# emmc.net
KiCad netlist of a schematic drawn in Altium Designer
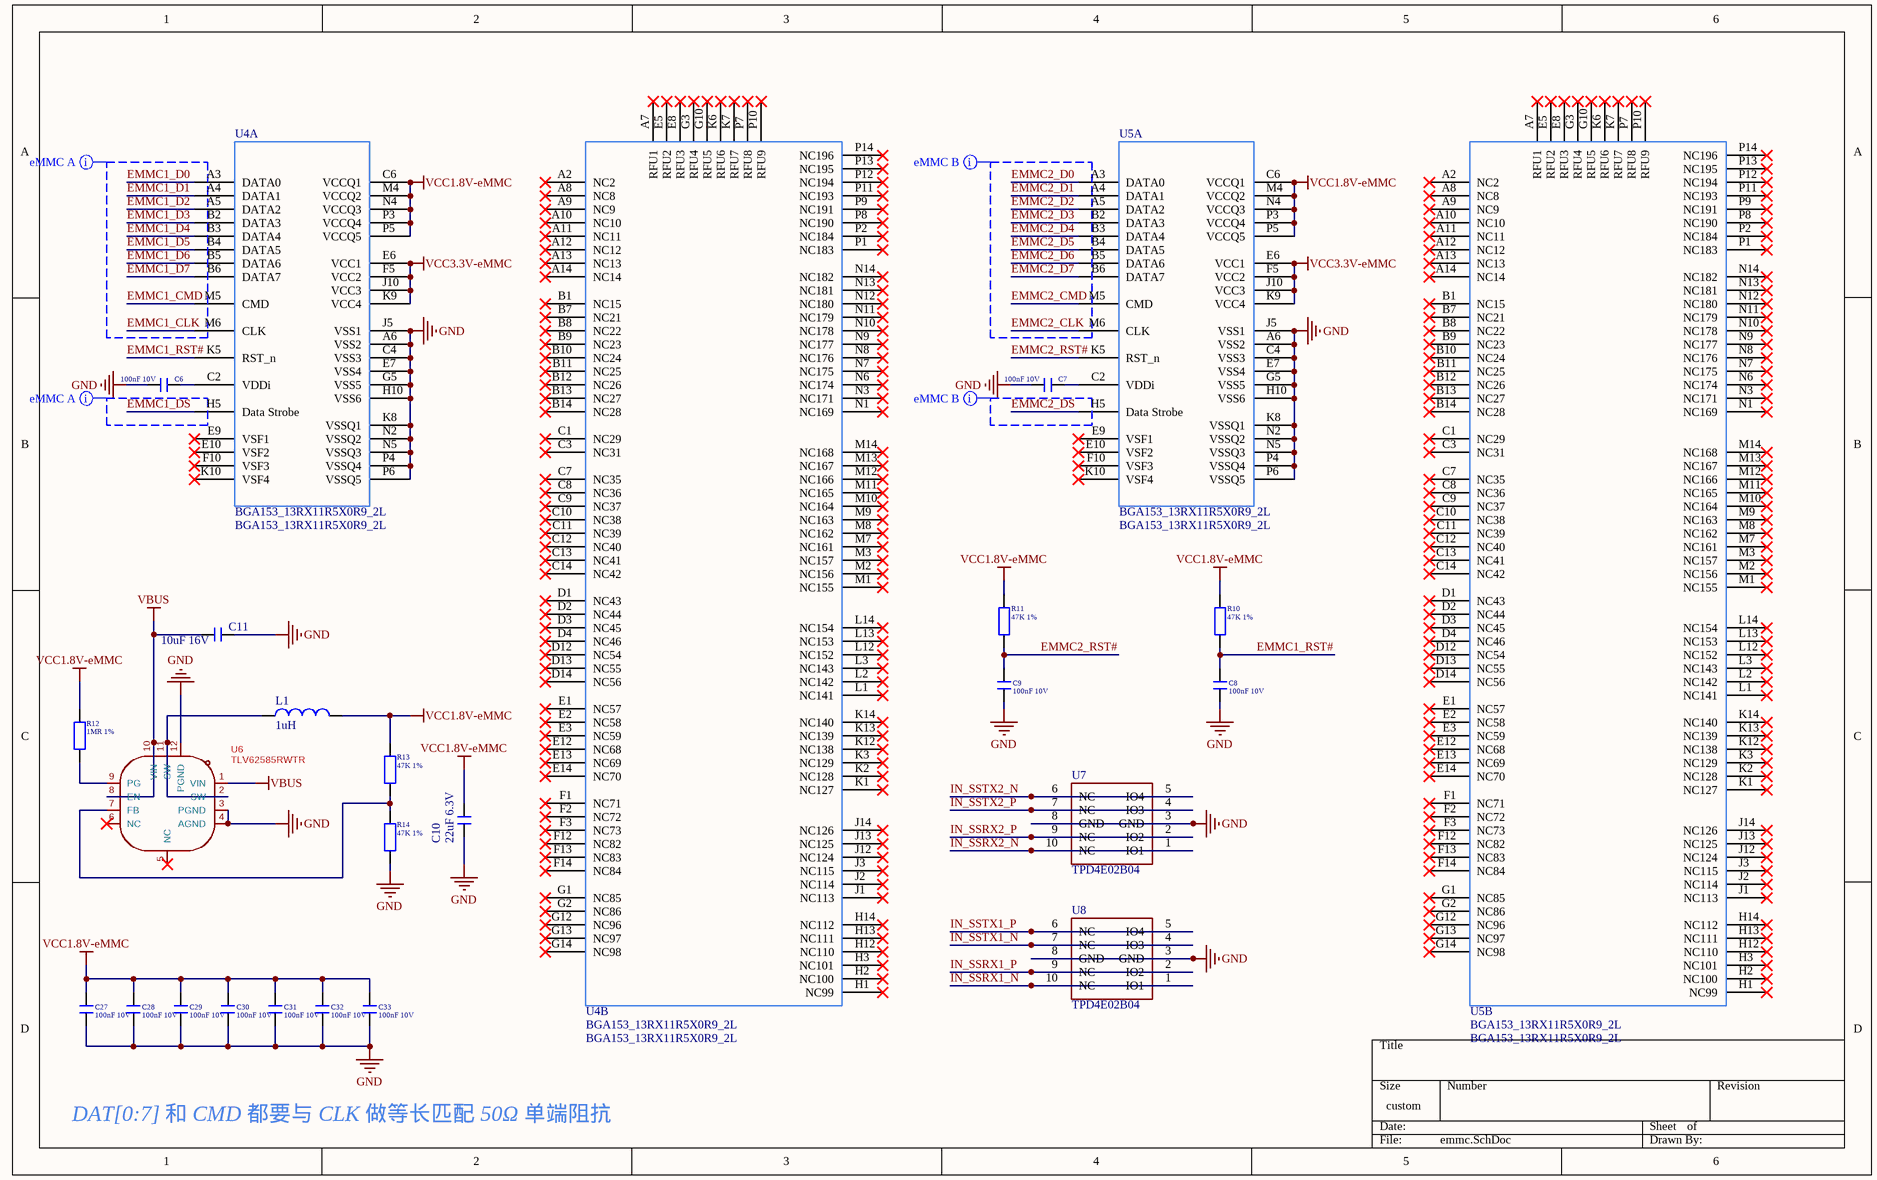
[diagram p0: emmc.SchDoc]

(export (version "E")
  (design (tool "Eeschema 10.0.6"))
  (components
    (comp (ref "C6")
      (value "100nF 10V")
      (footprint "C0402_NS")
      (description "无极性贴片电容")
      (libsource (lib "Capacitor") (part "C"))
    )
    (comp (ref "C7")
      (value "100nF 10V")
      (footprint "C0402_NS")
      (description "无极性贴片电容")
      (libsource (lib "Capacitor") (part "C"))
    )
    (comp (ref "C8")
      (value "100nF 10V")
      (footprint "C0402_NS")
      (description "无极性贴片电容")
      (libsource (lib "Capacitor") (part "C"))
    )
    (comp (ref "C9")
      (value "100nF 10V")
      (footprint "C0402_NS")
      (description "无极性贴片电容")
      (libsource (lib "Capacitor") (part "C"))
    )
    (comp (ref "C10")
      (value "22uF 6.3V")
      (footprint "C0402_NS")
      (description "无极性贴片电容")
      (libsource (lib "Capacitor") (part "C"))
    )
    (comp (ref "C11")
      (value "10uF 16V")
      (footprint "C0402_NS")
      (description "无极性贴片电容")
      (libsource (lib "Capacitor") (part "C"))
    )
    (comp (ref "C27")
      (value "100nF 10V")
      (footprint "C0603_NS")
      (description "无极性贴片电容")
      (libsource (lib "Capacitor") (part "C"))
    )
    (comp (ref "C28")
      (value "100nF 10V")
      (footprint "C0603_NS")
      (description "无极性贴片电容")
      (libsource (lib "Capacitor") (part "C"))
    )
    (comp (ref "C29")
      (value "100nF 10V")
      (footprint "C0603_NS")
      (description "无极性贴片电容")
      (libsource (lib "Capacitor") (part "C"))
    )
    (comp (ref "C30")
      (value "100nF 10V")
      (footprint "C0603_NS")
      (description "无极性贴片电容")
      (libsource (lib "Capacitor") (part "C"))
    )
    (comp (ref "C31")
      (value "100nF 10V")
      (footprint "C0603_NS")
      (description "无极性贴片电容")
      (libsource (lib "Capacitor") (part "C"))
    )
    (comp (ref "C32")
      (value "100nF 10V")
      (footprint "C0603_NS")
      (description "无极性贴片电容")
      (libsource (lib "Capacitor") (part "C"))
    )
    (comp (ref "C33")
      (value "100nF 10V")
      (footprint "C0603_NS")
      (description "无极性贴片电容")
      (libsource (lib "Capacitor") (part "C"))
    )
    (comp (ref "L1")
      (value "1uH")
      (footprint "L 0805_L")
      (description "小功率贴片电感")
      (libsource (lib "Inductor") (part "L"))
    )
    (comp (ref "R10")
      (value "47K 1%")
      (footprint "R0402_NS")
      (description "贴片电阻")
      (libsource (lib "Resistor") (part "R"))
    )
    (comp (ref "R11")
      (value "47K 1%")
      (footprint "R0402_NS")
      (description "贴片电阻")
      (libsource (lib "Resistor") (part "R"))
    )
    (comp (ref "R12")
      (value "1MR 1%")
      (footprint "R0402_NS")
      (description "贴片电阻")
      (libsource (lib "Resistor") (part "R"))
    )
    (comp (ref "R13")
      (value "47K 1%")
      (footprint "R0402_NS")
      (description "贴片电阻")
      (libsource (lib "Resistor") (part "R"))
    )
    (comp (ref "R14")
      (value "47K 1%")
      (footprint "R0402_NS")
      (description "贴片电阻")
      (libsource (lib "Resistor") (part "R"))
    )
    (comp (ref "U4")
      (value "BGA153_13RX11R5X0R9_2L")
      (footprint "FBGA-153_L13.0-W11.5-P0.50_KLMAG1JETD-B041")
      (description "EMMC_B153_2L,更好的满足工艺需求，Fanout方式部分走线跨接再球位上，挖除A1\\C5球位")
      (fields (field (name "PCB FOOTPRINT") "BGA153_13RX11R5X0R9_2L"))
      (libsource (lib "DDR2-DDR3-LPDDR4-RMII PHY") (part "INAND_EMMC_153_2L"))
    )
    (comp (ref "U5")
      (value "BGA153_13RX11R5X0R9_2L")
      (footprint "FBGA-153_L13.0-W11.5-P0.50_KLMAG1JETD-B041")
      (description "EMMC_B153_2L,更好的满足工艺需求，Fanout方式部分走线跨接再球位上，挖除A1\\C5球位")
      (fields (field (name "PCB FOOTPRINT") "BGA153_13RX11R5X0R9_2L"))
      (libsource (lib "DDR2-DDR3-LPDDR4-RMII PHY") (part "INAND_EMMC_153_2L"))
    )
    (comp (ref "U6")
      (value "TLV62585RWTR")
      (footprint "VQFN-HR-12_L2.0-W2.0-P0.50-BL")
      (description "功能类型:降压型;输出类型:可调;工作电压:2.5V~5.5V;输出电压:600mV~5.5V;输出电流:3A;")
      (fields (field (name "MANUFACTURER") "TI(德州仪器)"))
      (libsource (lib "DCDC Convert") (part "TLV62585RWTR"))
    )
    (comp (ref "U7")
      (value "TPD4E02B04")
      (footprint "DIO_TPD4E02B04DQAR")
      (description "ESD")
      (libsource (lib "Diode") (part "TPD4E02B04"))
    )
    (comp (ref "U8")
      (value "TPD4E02B04")
      (footprint "DIO_TPD4E02B04DQAR")
      (description "ESD")
      (libsource (lib "Diode") (part "TPD4E02B04"))
    )
  )
  (nets
    (net (code "1") (name "/EMMC1_CLK") (class "Default")
      (node (ref "U4") (pin "M6") (pinfunction "CLK_M6") (pintype "passive"))
    )
    (net (code "2") (name "/EMMC1_CMD") (class "Default")
      (node (ref "U4") (pin "M5") (pinfunction "CMD_M5") (pintype "passive"))
    )
    (net (code "3") (name "/EMMC1_D0") (class "Default")
      (node (ref "U4") (pin "A3") (pinfunction "DATA0_A3") (pintype "passive"))
    )
    (net (code "4") (name "/EMMC1_D1") (class "Default")
      (node (ref "U4") (pin "A4") (pinfunction "DATA1_A4") (pintype "passive"))
    )
    (net (code "5") (name "/EMMC1_D2") (class "Default")
      (node (ref "U4") (pin "A5") (pinfunction "DATA2_A5") (pintype "passive"))
    )
    (net (code "6") (name "/EMMC1_D3") (class "Default")
      (node (ref "U4") (pin "B2") (pinfunction "DATA3_B2") (pintype "passive"))
    )
    (net (code "7") (name "/EMMC1_D4") (class "Default")
      (node (ref "U4") (pin "B3") (pinfunction "DATA4_B3") (pintype "passive"))
    )
    (net (code "8") (name "/EMMC1_D5") (class "Default")
      (node (ref "U4") (pin "B4") (pinfunction "DATA5_B4") (pintype "passive"))
    )
    (net (code "9") (name "/EMMC1_D6") (class "Default")
      (node (ref "U4") (pin "B5") (pinfunction "DATA6_B5") (pintype "passive"))
    )
    (net (code "10") (name "/EMMC1_D7") (class "Default")
      (node (ref "U4") (pin "B6") (pinfunction "DATA7_B6") (pintype "passive"))
    )
    (net (code "11") (name "/EMMC1_DS") (class "Default")
      (node (ref "U4") (pin "H5") (pinfunction "Data_Strobe_H5") (pintype "passive"))
    )
    (net (code "12") (name "/EMMC1_RST#") (class "Default")
      (node (ref "C8") (pin "1") (pinfunction "1_1") (pintype "passive"))
      (node (ref "R10") (pin "2") (pinfunction "2_2") (pintype "passive"))
      (node (ref "U4") (pin "K5") (pinfunction "RST_n_K5") (pintype "passive"))
    )
    (net (code "13") (name "/EMMC2_CLK") (class "Default")
      (node (ref "U5") (pin "M6") (pinfunction "CLK_M6") (pintype "passive"))
    )
    (net (code "14") (name "/EMMC2_CMD") (class "Default")
      (node (ref "U5") (pin "M5") (pinfunction "CMD_M5") (pintype "passive"))
    )
    (net (code "15") (name "/EMMC2_D0") (class "Default")
      (node (ref "U5") (pin "A3") (pinfunction "DATA0_A3") (pintype "passive"))
    )
    (net (code "16") (name "/EMMC2_D1") (class "Default")
      (node (ref "U5") (pin "A4") (pinfunction "DATA1_A4") (pintype "passive"))
    )
    (net (code "17") (name "/EMMC2_D2") (class "Default")
      (node (ref "U5") (pin "A5") (pinfunction "DATA2_A5") (pintype "passive"))
    )
    (net (code "18") (name "/EMMC2_D3") (class "Default")
      (node (ref "U5") (pin "B2") (pinfunction "DATA3_B2") (pintype "passive"))
    )
    (net (code "19") (name "/EMMC2_D4") (class "Default")
      (node (ref "U5") (pin "B3") (pinfunction "DATA4_B3") (pintype "passive"))
    )
    (net (code "20") (name "/EMMC2_D5") (class "Default")
      (node (ref "U5") (pin "B4") (pinfunction "DATA5_B4") (pintype "passive"))
    )
    (net (code "21") (name "/EMMC2_D6") (class "Default")
      (node (ref "U5") (pin "B5") (pinfunction "DATA6_B5") (pintype "passive"))
    )
    (net (code "22") (name "/EMMC2_D7") (class "Default")
      (node (ref "U5") (pin "B6") (pinfunction "DATA7_B6") (pintype "passive"))
    )
    (net (code "23") (name "/EMMC2_DS") (class "Default")
      (node (ref "U5") (pin "H5") (pinfunction "Data_Strobe_H5") (pintype "passive"))
    )
    (net (code "24") (name "/EMMC2_RST#") (class "Default")
      (node (ref "C9") (pin "1") (pinfunction "1_1") (pintype "passive"))
      (node (ref "R11") (pin "2") (pinfunction "2_2") (pintype "passive"))
      (node (ref "U5") (pin "K5") (pinfunction "RST_n_K5") (pintype "passive"))
    )
    (net (code "25") (name "/IN_SSRX1_N") (class "Default")
      (node (ref "U8") (pin "1") (pinfunction "IO1_1") (pintype "passive"))
      (node (ref "U8") (pin "10") (pinfunction "NC_10") (pintype "passive"))
    )
    (net (code "26") (name "/IN_SSRX1_P") (class "Default")
      (node (ref "U8") (pin "2") (pinfunction "IO2_2") (pintype "passive"))
      (node (ref "U8") (pin "9") (pinfunction "NC_9") (pintype "passive"))
    )
    (net (code "27") (name "/IN_SSRX2_N") (class "Default")
      (node (ref "U7") (pin "1") (pinfunction "IO1_1") (pintype "passive"))
      (node (ref "U7") (pin "10") (pinfunction "NC_10") (pintype "passive"))
    )
    (net (code "28") (name "/IN_SSRX2_P") (class "Default")
      (node (ref "U7") (pin "2") (pinfunction "IO2_2") (pintype "passive"))
      (node (ref "U7") (pin "9") (pinfunction "NC_9") (pintype "passive"))
    )
    (net (code "29") (name "/IN_SSTX1_N") (class "Default")
      (node (ref "U8") (pin "4") (pinfunction "IO3_4") (pintype "passive"))
      (node (ref "U8") (pin "7") (pinfunction "NC_7") (pintype "passive"))
    )
    (net (code "30") (name "/IN_SSTX1_P") (class "Default")
      (node (ref "U8") (pin "5") (pinfunction "IO4_5") (pintype "passive"))
      (node (ref "U8") (pin "6") (pinfunction "NC_6") (pintype "passive"))
    )
    (net (code "31") (name "/IN_SSTX2_N") (class "Default")
      (node (ref "U7") (pin "5") (pinfunction "IO4_5") (pintype "passive"))
      (node (ref "U7") (pin "6") (pinfunction "NC_6") (pintype "passive"))
    )
    (net (code "32") (name "/IN_SSTX2_P") (class "Default")
      (node (ref "U7") (pin "4") (pinfunction "IO3_4") (pintype "passive"))
      (node (ref "U7") (pin "7") (pinfunction "NC_7") (pintype "passive"))
    )
    (net (code "33") (name "GND") (class "Default")
      (node (ref "C10") (pin "1") (pinfunction "1_1") (pintype "passive"))
      (node (ref "C11") (pin "1") (pinfunction "1_1") (pintype "passive"))
      (node (ref "C27") (pin "2") (pinfunction "2_2") (pintype "passive"))
      (node (ref "C28") (pin "2") (pinfunction "2_2") (pintype "passive"))
      (node (ref "C29") (pin "2") (pinfunction "2_2") (pintype "passive"))
      (node (ref "C30") (pin "2") (pinfunction "2_2") (pintype "passive"))
      (node (ref "C31") (pin "2") (pinfunction "2_2") (pintype "passive"))
      (node (ref "C32") (pin "2") (pinfunction "2_2") (pintype "passive"))
      (node (ref "C33") (pin "2") (pinfunction "2_2") (pintype "passive"))
      (node (ref "C6") (pin "2") (pinfunction "2_2") (pintype "passive"))
      (node (ref "C7") (pin "2") (pinfunction "2_2") (pintype "passive"))
      (node (ref "C8") (pin "2") (pinfunction "2_2") (pintype "passive"))
      (node (ref "C9") (pin "2") (pinfunction "2_2") (pintype "passive"))
      (node (ref "R14") (pin "2") (pinfunction "2_2") (pintype "passive"))
      (node (ref "U4") (pin "A6") (pinfunction "VSS2_A6") (pintype "passive"))
      (node (ref "U4") (pin "C4") (pinfunction "VSS3_C4") (pintype "passive"))
      (node (ref "U4") (pin "E7") (pinfunction "VSS4_E7") (pintype "passive"))
      (node (ref "U4") (pin "G5") (pinfunction "VSS5_G5") (pintype "passive"))
      (node (ref "U4") (pin "H10") (pinfunction "VSS6_H10") (pintype "passive"))
      (node (ref "U4") (pin "J5") (pinfunction "VSS1_J5") (pintype "passive"))
      (node (ref "U4") (pin "K8") (pinfunction "VSSQ1_K8") (pintype "passive"))
      (node (ref "U4") (pin "N2") (pinfunction "VSSQ2_N2") (pintype "passive"))
      (node (ref "U4") (pin "N5") (pinfunction "VSSQ3_N5") (pintype "passive"))
      (node (ref "U4") (pin "P4") (pinfunction "VSSQ4_P4") (pintype "passive"))
      (node (ref "U4") (pin "P6") (pinfunction "VSSQ5_P6") (pintype "passive"))
      (node (ref "U5") (pin "A6") (pinfunction "VSS2_A6") (pintype "passive"))
      (node (ref "U5") (pin "C4") (pinfunction "VSS3_C4") (pintype "passive"))
      (node (ref "U5") (pin "E7") (pinfunction "VSS4_E7") (pintype "passive"))
      (node (ref "U5") (pin "G5") (pinfunction "VSS5_G5") (pintype "passive"))
      (node (ref "U5") (pin "H10") (pinfunction "VSS6_H10") (pintype "passive"))
      (node (ref "U5") (pin "J5") (pinfunction "VSS1_J5") (pintype "passive"))
      (node (ref "U5") (pin "K8") (pinfunction "VSSQ1_K8") (pintype "passive"))
      (node (ref "U5") (pin "N2") (pinfunction "VSSQ2_N2") (pintype "passive"))
      (node (ref "U5") (pin "N5") (pinfunction "VSSQ3_N5") (pintype "passive"))
      (node (ref "U5") (pin "P4") (pinfunction "VSSQ4_P4") (pintype "passive"))
      (node (ref "U5") (pin "P6") (pinfunction "VSSQ5_P6") (pintype "passive"))
      (node (ref "U6") (pin "12") (pinfunction "PGND_12") (pintype "passive"))
      (node (ref "U6") (pin "3") (pinfunction "PGND_3") (pintype "passive"))
      (node (ref "U6") (pin "4") (pinfunction "AGND_4") (pintype "passive"))
      (node (ref "U7") (pin "3") (pinfunction "GND_3") (pintype "passive"))
      (node (ref "U7") (pin "8") (pinfunction "GND_8") (pintype "passive"))
      (node (ref "U8") (pin "3") (pinfunction "GND_3") (pintype "passive"))
      (node (ref "U8") (pin "8") (pinfunction "GND_8") (pintype "passive"))
    )
    (net (code "34") (name "Net-(L1-Pad1)") (class "Default")
      (node (ref "L1") (pin "1") (pinfunction "1_1") (pintype "passive"))
      (node (ref "U6") (pin "11") (pinfunction "SW_11") (pintype "passive"))
      (node (ref "U6") (pin "2") (pinfunction "SW_2") (pintype "passive"))
    )
    (net (code "35") (name "Net-(U4A-VDDi)") (class "Default")
      (node (ref "C6") (pin "1") (pinfunction "1_1") (pintype "passive"))
      (node (ref "U4") (pin "C2") (pinfunction "VDDi_C2") (pintype "passive"))
    )
    (net (code "36") (name "Net-(U5A-VDDi)") (class "Default")
      (node (ref "C7") (pin "1") (pinfunction "1_1") (pintype "passive"))
      (node (ref "U5") (pin "C2") (pinfunction "VDDi_C2") (pintype "passive"))
    )
    (net (code "37") (name "Net-(U6-FB)") (class "Default")
      (node (ref "R13") (pin "2") (pinfunction "2_2") (pintype "passive"))
      (node (ref "R14") (pin "1") (pinfunction "1_1") (pintype "passive"))
      (node (ref "U6") (pin "7") (pinfunction "FB_7") (pintype "passive"))
    )
    (net (code "38") (name "Net-(U6-PG)") (class "Default")
      (node (ref "R12") (pin "2") (pinfunction "2_2") (pintype "passive"))
      (node (ref "U6") (pin "9") (pinfunction "PG_9") (pintype "passive"))
    )
    (net (code "39") (name "VBUS") (class "Default")
      (node (ref "C11") (pin "2") (pinfunction "2_2") (pintype "passive"))
      (node (ref "U6") (pin "1") (pinfunction "VIN_1") (pintype "passive"))
      (node (ref "U6") (pin "10") (pinfunction "VIN_10") (pintype "passive"))
      (node (ref "U6") (pin "8") (pinfunction "EN_8") (pintype "passive"))
    )
    (net (code "40") (name "VCC1.8V-eMMC") (class "Default")
      (node (ref "C10") (pin "2") (pinfunction "2_2") (pintype "passive"))
      (node (ref "C27") (pin "1") (pinfunction "1_1") (pintype "passive"))
      (node (ref "C28") (pin "1") (pinfunction "1_1") (pintype "passive"))
      (node (ref "C29") (pin "1") (pinfunction "1_1") (pintype "passive"))
      (node (ref "C30") (pin "1") (pinfunction "1_1") (pintype "passive"))
      (node (ref "C31") (pin "1") (pinfunction "1_1") (pintype "passive"))
      (node (ref "C32") (pin "1") (pinfunction "1_1") (pintype "passive"))
      (node (ref "C33") (pin "1") (pinfunction "1_1") (pintype "passive"))
      (node (ref "L1") (pin "2") (pinfunction "2_2") (pintype "passive"))
      (node (ref "R10") (pin "1") (pinfunction "1_1") (pintype "passive"))
      (node (ref "R11") (pin "1") (pinfunction "1_1") (pintype "passive"))
      (node (ref "R12") (pin "1") (pinfunction "1_1") (pintype "passive"))
      (node (ref "R13") (pin "1") (pinfunction "1_1") (pintype "passive"))
      (node (ref "U4") (pin "C6") (pinfunction "VCCQ1_C6") (pintype "passive"))
      (node (ref "U4") (pin "M4") (pinfunction "VCCQ2_M4") (pintype "passive"))
      (node (ref "U4") (pin "N4") (pinfunction "VCCQ3_N4") (pintype "passive"))
      (node (ref "U4") (pin "P3") (pinfunction "VCCQ4_P3") (pintype "passive"))
      (node (ref "U4") (pin "P5") (pinfunction "VCCQ5_P5") (pintype "passive"))
      (node (ref "U5") (pin "C6") (pinfunction "VCCQ1_C6") (pintype "passive"))
      (node (ref "U5") (pin "M4") (pinfunction "VCCQ2_M4") (pintype "passive"))
      (node (ref "U5") (pin "N4") (pinfunction "VCCQ3_N4") (pintype "passive"))
      (node (ref "U5") (pin "P3") (pinfunction "VCCQ4_P3") (pintype "passive"))
      (node (ref "U5") (pin "P5") (pinfunction "VCCQ5_P5") (pintype "passive"))
    )
    (net (code "41") (name "VCC3.3V-eMMC") (class "Default")
      (node (ref "U4") (pin "E6") (pinfunction "VCC1_E6") (pintype "passive"))
      (node (ref "U4") (pin "F5") (pinfunction "VCC2_F5") (pintype "passive"))
      (node (ref "U4") (pin "J10") (pinfunction "VCC3_J10") (pintype "passive"))
      (node (ref "U4") (pin "K9") (pinfunction "VCC4_K9") (pintype "passive"))
      (node (ref "U5") (pin "E6") (pinfunction "VCC1_E6") (pintype "passive"))
      (node (ref "U5") (pin "F5") (pinfunction "VCC2_F5") (pintype "passive"))
      (node (ref "U5") (pin "J10") (pinfunction "VCC3_J10") (pintype "passive"))
      (node (ref "U5") (pin "K9") (pinfunction "VCC4_K9") (pintype "passive"))
    )
    (net (code "42") (name "unconnected-(U4A-VSF1-PadE9)") (class "Default")
      (node (ref "U4") (pin "E9") (pinfunction "VSF1_E9") (pintype "passive+no_connect"))
    )
    (net (code "43") (name "unconnected-(U4A-VSF2-PadE10)") (class "Default")
      (node (ref "U4") (pin "E10") (pinfunction "VSF2_E10") (pintype "passive+no_connect"))
    )
    (net (code "44") (name "unconnected-(U4A-VSF3-PadF10)") (class "Default")
      (node (ref "U4") (pin "F10") (pinfunction "VSF3_F10") (pintype "passive+no_connect"))
    )
    (net (code "45") (name "unconnected-(U4A-VSF4-PadK10)") (class "Default")
      (node (ref "U4") (pin "K10") (pinfunction "VSF4_K10") (pintype "passive+no_connect"))
    )
    (net (code "46") (name "unconnected-(U4B-NC2-PadA2)") (class "Default")
      (node (ref "U4") (pin "A2") (pinfunction "NC2_A2") (pintype "passive+no_connect"))
    )
    (net (code "47") (name "unconnected-(U4B-NC8-PadA8)") (class "Default")
      (node (ref "U4") (pin "A8") (pinfunction "NC8_A8") (pintype "passive+no_connect"))
    )
    (net (code "48") (name "unconnected-(U4B-NC9-PadA9)") (class "Default")
      (node (ref "U4") (pin "A9") (pinfunction "NC9_A9") (pintype "passive+no_connect"))
    )
    (net (code "49") (name "unconnected-(U4B-NC10-PadA10)") (class "Default")
      (node (ref "U4") (pin "A10") (pinfunction "NC10_A10") (pintype "passive+no_connect"))
    )
    (net (code "50") (name "unconnected-(U4B-NC11-PadA11)") (class "Default")
      (node (ref "U4") (pin "A11") (pinfunction "NC11_A11") (pintype "passive+no_connect"))
    )
    (net (code "51") (name "unconnected-(U4B-NC12-PadA12)") (class "Default")
      (node (ref "U4") (pin "A12") (pinfunction "NC12_A12") (pintype "passive+no_connect"))
    )
    (net (code "52") (name "unconnected-(U4B-NC13-PadA13)") (class "Default")
      (node (ref "U4") (pin "A13") (pinfunction "NC13_A13") (pintype "passive+no_connect"))
    )
    (net (code "53") (name "unconnected-(U4B-NC14-PadA14)") (class "Default")
      (node (ref "U4") (pin "A14") (pinfunction "NC14_A14") (pintype "passive+no_connect"))
    )
    (net (code "54") (name "unconnected-(U4B-NC15-PadB1)") (class "Default")
      (node (ref "U4") (pin "B1") (pinfunction "NC15_B1") (pintype "passive+no_connect"))
    )
    (net (code "55") (name "unconnected-(U4B-NC21-PadB7)") (class "Default")
      (node (ref "U4") (pin "B7") (pinfunction "NC21_B7") (pintype "passive+no_connect"))
    )
    (net (code "56") (name "unconnected-(U4B-NC22-PadB8)") (class "Default")
      (node (ref "U4") (pin "B8") (pinfunction "NC22_B8") (pintype "passive+no_connect"))
    )
    (net (code "57") (name "unconnected-(U4B-NC23-PadB9)") (class "Default")
      (node (ref "U4") (pin "B9") (pinfunction "NC23_B9") (pintype "passive+no_connect"))
    )
    (net (code "58") (name "unconnected-(U4B-NC24-PadB10)") (class "Default")
      (node (ref "U4") (pin "B10") (pinfunction "NC24_B10") (pintype "passive+no_connect"))
    )
    (net (code "59") (name "unconnected-(U4B-NC25-PadB11)") (class "Default")
      (node (ref "U4") (pin "B11") (pinfunction "NC25_B11") (pintype "passive+no_connect"))
    )
    (net (code "60") (name "unconnected-(U4B-NC26-PadB12)") (class "Default")
      (node (ref "U4") (pin "B12") (pinfunction "NC26_B12") (pintype "passive+no_connect"))
    )
    (net (code "61") (name "unconnected-(U4B-NC27-PadB13)") (class "Default")
      (node (ref "U4") (pin "B13") (pinfunction "NC27_B13") (pintype "passive+no_connect"))
    )
    (net (code "62") (name "unconnected-(U4B-NC28-PadB14)") (class "Default")
      (node (ref "U4") (pin "B14") (pinfunction "NC28_B14") (pintype "passive+no_connect"))
    )
    (net (code "63") (name "unconnected-(U4B-NC29-PadC1)") (class "Default")
      (node (ref "U4") (pin "C1") (pinfunction "NC29_C1") (pintype "passive+no_connect"))
    )
    (net (code "64") (name "unconnected-(U4B-NC31-PadC3)") (class "Default")
      (node (ref "U4") (pin "C3") (pinfunction "NC31_C3") (pintype "passive+no_connect"))
    )
    (net (code "65") (name "unconnected-(U4B-NC35-PadC7)") (class "Default")
      (node (ref "U4") (pin "C7") (pinfunction "NC35_C7") (pintype "passive+no_connect"))
    )
    (net (code "66") (name "unconnected-(U4B-NC36-PadC8)") (class "Default")
      (node (ref "U4") (pin "C8") (pinfunction "NC36_C8") (pintype "passive+no_connect"))
    )
    (net (code "67") (name "unconnected-(U4B-NC37-PadC9)") (class "Default")
      (node (ref "U4") (pin "C9") (pinfunction "NC37_C9") (pintype "passive+no_connect"))
    )
    (net (code "68") (name "unconnected-(U4B-NC38-PadC10)") (class "Default")
      (node (ref "U4") (pin "C10") (pinfunction "NC38_C10") (pintype "passive+no_connect"))
    )
    (net (code "69") (name "unconnected-(U4B-NC39-PadC11)") (class "Default")
      (node (ref "U4") (pin "C11") (pinfunction "NC39_C11") (pintype "passive+no_connect"))
    )
    (net (code "70") (name "unconnected-(U4B-NC40-PadC12)") (class "Default")
      (node (ref "U4") (pin "C12") (pinfunction "NC40_C12") (pintype "passive+no_connect"))
    )
    (net (code "71") (name "unconnected-(U4B-NC41-PadC13)") (class "Default")
      (node (ref "U4") (pin "C13") (pinfunction "NC41_C13") (pintype "passive+no_connect"))
    )
    (net (code "72") (name "unconnected-(U4B-NC42-PadC14)") (class "Default")
      (node (ref "U4") (pin "C14") (pinfunction "NC42_C14") (pintype "passive+no_connect"))
    )
    (net (code "73") (name "unconnected-(U4B-NC43-PadD1)") (class "Default")
      (node (ref "U4") (pin "D1") (pinfunction "NC43_D1") (pintype "passive+no_connect"))
    )
    (net (code "74") (name "unconnected-(U4B-NC44-PadD2)") (class "Default")
      (node (ref "U4") (pin "D2") (pinfunction "NC44_D2") (pintype "passive+no_connect"))
    )
    (net (code "75") (name "unconnected-(U4B-NC45-PadD3)") (class "Default")
      (node (ref "U4") (pin "D3") (pinfunction "NC45_D3") (pintype "passive+no_connect"))
    )
    (net (code "76") (name "unconnected-(U4B-NC46-PadD4)") (class "Default")
      (node (ref "U4") (pin "D4") (pinfunction "NC46_D4") (pintype "passive+no_connect"))
    )
    (net (code "77") (name "unconnected-(U4B-NC54-PadD12)") (class "Default")
      (node (ref "U4") (pin "D12") (pinfunction "NC54_D12") (pintype "passive+no_connect"))
    )
    (net (code "78") (name "unconnected-(U4B-NC55-PadD13)") (class "Default")
      (node (ref "U4") (pin "D13") (pinfunction "NC55_D13") (pintype "passive+no_connect"))
    )
    (net (code "79") (name "unconnected-(U4B-NC56-PadD14)") (class "Default")
      (node (ref "U4") (pin "D14") (pinfunction "NC56_D14") (pintype "passive+no_connect"))
    )
    (net (code "80") (name "unconnected-(U4B-NC57-PadE1)") (class "Default")
      (node (ref "U4") (pin "E1") (pinfunction "NC57_E1") (pintype "passive+no_connect"))
    )
    (net (code "81") (name "unconnected-(U4B-NC58-PadE2)") (class "Default")
      (node (ref "U4") (pin "E2") (pinfunction "NC58_E2") (pintype "passive+no_connect"))
    )
    (net (code "82") (name "unconnected-(U4B-NC59-PadE3)") (class "Default")
      (node (ref "U4") (pin "E3") (pinfunction "NC59_E3") (pintype "passive+no_connect"))
    )
    (net (code "83") (name "unconnected-(U4B-NC68-PadE12)") (class "Default")
      (node (ref "U4") (pin "E12") (pinfunction "NC68_E12") (pintype "passive+no_connect"))
    )
    (net (code "84") (name "unconnected-(U4B-NC69-PadE13)") (class "Default")
      (node (ref "U4") (pin "E13") (pinfunction "NC69_E13") (pintype "passive+no_connect"))
    )
    (net (code "85") (name "unconnected-(U4B-NC70-PadE14)") (class "Default")
      (node (ref "U4") (pin "E14") (pinfunction "NC70_E14") (pintype "passive+no_connect"))
    )
    (net (code "86") (name "unconnected-(U4B-NC71-PadF1)") (class "Default")
      (node (ref "U4") (pin "F1") (pinfunction "NC71_F1") (pintype "passive+no_connect"))
    )
    (net (code "87") (name "unconnected-(U4B-NC72-PadF2)") (class "Default")
      (node (ref "U4") (pin "F2") (pinfunction "NC72_F2") (pintype "passive+no_connect"))
    )
    (net (code "88") (name "unconnected-(U4B-NC73-PadF3)") (class "Default")
      (node (ref "U4") (pin "F3") (pinfunction "NC73_F3") (pintype "passive+no_connect"))
    )
    (net (code "89") (name "unconnected-(U4B-NC82-PadF12)") (class "Default")
      (node (ref "U4") (pin "F12") (pinfunction "NC82_F12") (pintype "passive+no_connect"))
    )
    (net (code "90") (name "unconnected-(U4B-NC83-PadF13)") (class "Default")
      (node (ref "U4") (pin "F13") (pinfunction "NC83_F13") (pintype "passive+no_connect"))
    )
    (net (code "91") (name "unconnected-(U4B-NC84-PadF14)") (class "Default")
      (node (ref "U4") (pin "F14") (pinfunction "NC84_F14") (pintype "passive+no_connect"))
    )
    (net (code "92") (name "unconnected-(U4B-NC85-PadG1)") (class "Default")
      (node (ref "U4") (pin "G1") (pinfunction "NC85_G1") (pintype "passive+no_connect"))
    )
    (net (code "93") (name "unconnected-(U4B-NC86-PadG2)") (class "Default")
      (node (ref "U4") (pin "G2") (pinfunction "NC86_G2") (pintype "passive+no_connect"))
    )
    (net (code "94") (name "unconnected-(U4B-NC96-PadG12)") (class "Default")
      (node (ref "U4") (pin "G12") (pinfunction "NC96_G12") (pintype "passive+no_connect"))
    )
    (net (code "95") (name "unconnected-(U4B-NC97-PadG13)") (class "Default")
      (node (ref "U4") (pin "G13") (pinfunction "NC97_G13") (pintype "passive+no_connect"))
    )
    (net (code "96") (name "unconnected-(U4B-NC98-PadG14)") (class "Default")
      (node (ref "U4") (pin "G14") (pinfunction "NC98_G14") (pintype "passive+no_connect"))
    )
    (net (code "97") (name "unconnected-(U4B-NC99-PadH1)") (class "Default")
      (node (ref "U4") (pin "H1") (pinfunction "NC99_H1") (pintype "passive+no_connect"))
    )
    (net (code "98") (name "unconnected-(U4B-NC100-PadH2)") (class "Default")
      (node (ref "U4") (pin "H2") (pinfunction "NC100_H2") (pintype "passive+no_connect"))
    )
    (net (code "99") (name "unconnected-(U4B-NC101-PadH3)") (class "Default")
      (node (ref "U4") (pin "H3") (pinfunction "NC101_H3") (pintype "passive+no_connect"))
    )
    (net (code "100") (name "unconnected-(U4B-NC110-PadH12)") (class "Default")
      (node (ref "U4") (pin "H12") (pinfunction "NC110_H12") (pintype "passive+no_connect"))
    )
    (net (code "101") (name "unconnected-(U4B-NC111-PadH13)") (class "Default")
      (node (ref "U4") (pin "H13") (pinfunction "NC111_H13") (pintype "passive+no_connect"))
    )
    (net (code "102") (name "unconnected-(U4B-NC112-PadH14)") (class "Default")
      (node (ref "U4") (pin "H14") (pinfunction "NC112_H14") (pintype "passive+no_connect"))
    )
    (net (code "103") (name "unconnected-(U4B-NC113-PadJ1)") (class "Default")
      (node (ref "U4") (pin "J1") (pinfunction "NC113_J1") (pintype "passive+no_connect"))
    )
    (net (code "104") (name "unconnected-(U4B-NC114-PadJ2)") (class "Default")
      (node (ref "U4") (pin "J2") (pinfunction "NC114_J2") (pintype "passive+no_connect"))
    )
    (net (code "105") (name "unconnected-(U4B-NC115-PadJ3)") (class "Default")
      (node (ref "U4") (pin "J3") (pinfunction "NC115_J3") (pintype "passive+no_connect"))
    )
    (net (code "106") (name "unconnected-(U4B-NC124-PadJ12)") (class "Default")
      (node (ref "U4") (pin "J12") (pinfunction "NC124_J12") (pintype "passive+no_connect"))
    )
    (net (code "107") (name "unconnected-(U4B-NC125-PadJ13)") (class "Default")
      (node (ref "U4") (pin "J13") (pinfunction "NC125_J13") (pintype "passive+no_connect"))
    )
    (net (code "108") (name "unconnected-(U4B-NC126-PadJ14)") (class "Default")
      (node (ref "U4") (pin "J14") (pinfunction "NC126_J14") (pintype "passive+no_connect"))
    )
    (net (code "109") (name "unconnected-(U4B-NC127-PadK1)") (class "Default")
      (node (ref "U4") (pin "K1") (pinfunction "NC127_K1") (pintype "passive+no_connect"))
    )
    (net (code "110") (name "unconnected-(U4B-NC128-PadK2)") (class "Default")
      (node (ref "U4") (pin "K2") (pinfunction "NC128_K2") (pintype "passive+no_connect"))
    )
    (net (code "111") (name "unconnected-(U4B-NC129-PadK3)") (class "Default")
      (node (ref "U4") (pin "K3") (pinfunction "NC129_K3") (pintype "passive+no_connect"))
    )
    (net (code "112") (name "unconnected-(U4B-NC138-PadK12)") (class "Default")
      (node (ref "U4") (pin "K12") (pinfunction "NC138_K12") (pintype "passive+no_connect"))
    )
    (net (code "113") (name "unconnected-(U4B-NC139-PadK13)") (class "Default")
      (node (ref "U4") (pin "K13") (pinfunction "NC139_K13") (pintype "passive+no_connect"))
    )
    (net (code "114") (name "unconnected-(U4B-NC140-PadK14)") (class "Default")
      (node (ref "U4") (pin "K14") (pinfunction "NC140_K14") (pintype "passive+no_connect"))
    )
    (net (code "115") (name "unconnected-(U4B-NC141-PadL1)") (class "Default")
      (node (ref "U4") (pin "L1") (pinfunction "NC141_L1") (pintype "passive+no_connect"))
    )
    (net (code "116") (name "unconnected-(U4B-NC142-PadL2)") (class "Default")
      (node (ref "U4") (pin "L2") (pinfunction "NC142_L2") (pintype "passive+no_connect"))
    )
    (net (code "117") (name "unconnected-(U4B-NC143-PadL3)") (class "Default")
      (node (ref "U4") (pin "L3") (pinfunction "NC143_L3") (pintype "passive+no_connect"))
    )
    (net (code "118") (name "unconnected-(U4B-NC152-PadL12)") (class "Default")
      (node (ref "U4") (pin "L12") (pinfunction "NC152_L12") (pintype "passive+no_connect"))
    )
    (net (code "119") (name "unconnected-(U4B-NC153-PadL13)") (class "Default")
      (node (ref "U4") (pin "L13") (pinfunction "NC153_L13") (pintype "passive+no_connect"))
    )
    (net (code "120") (name "unconnected-(U4B-NC154-PadL14)") (class "Default")
      (node (ref "U4") (pin "L14") (pinfunction "NC154_L14") (pintype "passive+no_connect"))
    )
    (net (code "121") (name "unconnected-(U4B-NC155-PadM1)") (class "Default")
      (node (ref "U4") (pin "M1") (pinfunction "NC155_M1") (pintype "passive+no_connect"))
    )
    (net (code "122") (name "unconnected-(U4B-NC156-PadM2)") (class "Default")
      (node (ref "U4") (pin "M2") (pinfunction "NC156_M2") (pintype "passive+no_connect"))
    )
    (net (code "123") (name "unconnected-(U4B-NC157-PadM3)") (class "Default")
      (node (ref "U4") (pin "M3") (pinfunction "NC157_M3") (pintype "passive+no_connect"))
    )
    (net (code "124") (name "unconnected-(U4B-NC161-PadM7)") (class "Default")
      (node (ref "U4") (pin "M7") (pinfunction "NC161_M7") (pintype "passive+no_connect"))
    )
    (net (code "125") (name "unconnected-(U4B-NC162-PadM8)") (class "Default")
      (node (ref "U4") (pin "M8") (pinfunction "NC162_M8") (pintype "passive+no_connect"))
    )
    (net (code "126") (name "unconnected-(U4B-NC163-PadM9)") (class "Default")
      (node (ref "U4") (pin "M9") (pinfunction "NC163_M9") (pintype "passive+no_connect"))
    )
    (net (code "127") (name "unconnected-(U4B-NC164-PadM10)") (class "Default")
      (node (ref "U4") (pin "M10") (pinfunction "NC164_M10") (pintype "passive+no_connect"))
    )
    (net (code "128") (name "unconnected-(U4B-NC165-PadM11)") (class "Default")
      (node (ref "U4") (pin "M11") (pinfunction "NC165_M11") (pintype "passive+no_connect"))
    )
    (net (code "129") (name "unconnected-(U4B-NC166-PadM12)") (class "Default")
      (node (ref "U4") (pin "M12") (pinfunction "NC166_M12") (pintype "passive+no_connect"))
    )
    (net (code "130") (name "unconnected-(U4B-NC167-PadM13)") (class "Default")
      (node (ref "U4") (pin "M13") (pinfunction "NC167_M13") (pintype "passive+no_connect"))
    )
    (net (code "131") (name "unconnected-(U4B-NC168-PadM14)") (class "Default")
      (node (ref "U4") (pin "M14") (pinfunction "NC168_M14") (pintype "passive+no_connect"))
    )
    (net (code "132") (name "unconnected-(U4B-NC169-PadN1)") (class "Default")
      (node (ref "U4") (pin "N1") (pinfunction "NC169_N1") (pintype "passive+no_connect"))
    )
    (net (code "133") (name "unconnected-(U4B-NC171-PadN3)") (class "Default")
      (node (ref "U4") (pin "N3") (pinfunction "NC171_N3") (pintype "passive+no_connect"))
    )
    (net (code "134") (name "unconnected-(U4B-NC174-PadN6)") (class "Default")
      (node (ref "U4") (pin "N6") (pinfunction "NC174_N6") (pintype "passive+no_connect"))
    )
    (net (code "135") (name "unconnected-(U4B-NC175-PadN7)") (class "Default")
      (node (ref "U4") (pin "N7") (pinfunction "NC175_N7") (pintype "passive+no_connect"))
    )
    (net (code "136") (name "unconnected-(U4B-NC176-PadN8)") (class "Default")
      (node (ref "U4") (pin "N8") (pinfunction "NC176_N8") (pintype "passive+no_connect"))
    )
    (net (code "137") (name "unconnected-(U4B-NC177-PadN9)") (class "Default")
      (node (ref "U4") (pin "N9") (pinfunction "NC177_N9") (pintype "passive+no_connect"))
    )
    (net (code "138") (name "unconnected-(U4B-NC178-PadN10)") (class "Default")
      (node (ref "U4") (pin "N10") (pinfunction "NC178_N10") (pintype "passive+no_connect"))
    )
    (net (code "139") (name "unconnected-(U4B-NC179-PadN11)") (class "Default")
      (node (ref "U4") (pin "N11") (pinfunction "NC179_N11") (pintype "passive+no_connect"))
    )
    (net (code "140") (name "unconnected-(U4B-NC180-PadN12)") (class "Default")
      (node (ref "U4") (pin "N12") (pinfunction "NC180_N12") (pintype "passive+no_connect"))
    )
    (net (code "141") (name "unconnected-(U4B-NC181-PadN13)") (class "Default")
      (node (ref "U4") (pin "N13") (pinfunction "NC181_N13") (pintype "passive+no_connect"))
    )
    (net (code "142") (name "unconnected-(U4B-NC182-PadN14)") (class "Default")
      (node (ref "U4") (pin "N14") (pinfunction "NC182_N14") (pintype "passive+no_connect"))
    )
    (net (code "143") (name "unconnected-(U4B-NC183-PadP1)") (class "Default")
      (node (ref "U4") (pin "P1") (pinfunction "NC183_P1") (pintype "passive+no_connect"))
    )
    (net (code "144") (name "unconnected-(U4B-NC184-PadP2)") (class "Default")
      (node (ref "U4") (pin "P2") (pinfunction "NC184_P2") (pintype "passive+no_connect"))
    )
    (net (code "145") (name "unconnected-(U4B-NC190-PadP8)") (class "Default")
      (node (ref "U4") (pin "P8") (pinfunction "NC190_P8") (pintype "passive+no_connect"))
    )
    (net (code "146") (name "unconnected-(U4B-NC191-PadP9)") (class "Default")
      (node (ref "U4") (pin "P9") (pinfunction "NC191_P9") (pintype "passive+no_connect"))
    )
    (net (code "147") (name "unconnected-(U4B-NC193-PadP11)") (class "Default")
      (node (ref "U4") (pin "P11") (pinfunction "NC193_P11") (pintype "passive+no_connect"))
    )
    (net (code "148") (name "unconnected-(U4B-NC194-PadP12)") (class "Default")
      (node (ref "U4") (pin "P12") (pinfunction "NC194_P12") (pintype "passive+no_connect"))
    )
    (net (code "149") (name "unconnected-(U4B-NC195-PadP13)") (class "Default")
      (node (ref "U4") (pin "P13") (pinfunction "NC195_P13") (pintype "passive+no_connect"))
    )
    (net (code "150") (name "unconnected-(U4B-NC196-PadP14)") (class "Default")
      (node (ref "U4") (pin "P14") (pinfunction "NC196_P14") (pintype "passive+no_connect"))
    )
    (net (code "151") (name "unconnected-(U4B-RFU1-PadA7)") (class "Default")
      (node (ref "U4") (pin "A7") (pinfunction "RFU1_A7") (pintype "passive+no_connect"))
    )
    (net (code "152") (name "unconnected-(U4B-RFU2-PadE5)") (class "Default")
      (node (ref "U4") (pin "E5") (pinfunction "RFU2_E5") (pintype "passive+no_connect"))
    )
    (net (code "153") (name "unconnected-(U4B-RFU3-PadE8)") (class "Default")
      (node (ref "U4") (pin "E8") (pinfunction "RFU3_E8") (pintype "passive+no_connect"))
    )
    (net (code "154") (name "unconnected-(U4B-RFU4-PadG3)") (class "Default")
      (node (ref "U4") (pin "G3") (pinfunction "RFU4_G3") (pintype "passive+no_connect"))
    )
    (net (code "155") (name "unconnected-(U4B-RFU5-PadG10)") (class "Default")
      (node (ref "U4") (pin "G10") (pinfunction "RFU5_G10") (pintype "passive+no_connect"))
    )
    (net (code "156") (name "unconnected-(U4B-RFU6-PadK6)") (class "Default")
      (node (ref "U4") (pin "K6") (pinfunction "RFU6_K6") (pintype "passive+no_connect"))
    )
    (net (code "157") (name "unconnected-(U4B-RFU7-PadK7)") (class "Default")
      (node (ref "U4") (pin "K7") (pinfunction "RFU7_K7") (pintype "passive+no_connect"))
    )
    (net (code "158") (name "unconnected-(U4B-RFU8-PadP7)") (class "Default")
      (node (ref "U4") (pin "P7") (pinfunction "RFU8_P7") (pintype "passive+no_connect"))
    )
    (net (code "159") (name "unconnected-(U4B-RFU9-PadP10)") (class "Default")
      (node (ref "U4") (pin "P10") (pinfunction "RFU9_P10") (pintype "passive+no_connect"))
    )
    (net (code "160") (name "unconnected-(U5A-VSF1-PadE9)") (class "Default")
      (node (ref "U5") (pin "E9") (pinfunction "VSF1_E9") (pintype "passive+no_connect"))
    )
    (net (code "161") (name "unconnected-(U5A-VSF2-PadE10)") (class "Default")
      (node (ref "U5") (pin "E10") (pinfunction "VSF2_E10") (pintype "passive+no_connect"))
    )
    (net (code "162") (name "unconnected-(U5A-VSF3-PadF10)") (class "Default")
      (node (ref "U5") (pin "F10") (pinfunction "VSF3_F10") (pintype "passive+no_connect"))
    )
    (net (code "163") (name "unconnected-(U5A-VSF4-PadK10)") (class "Default")
      (node (ref "U5") (pin "K10") (pinfunction "VSF4_K10") (pintype "passive+no_connect"))
    )
    (net (code "164") (name "unconnected-(U5B-NC2-PadA2)") (class "Default")
      (node (ref "U5") (pin "A2") (pinfunction "NC2_A2") (pintype "passive+no_connect"))
    )
    (net (code "165") (name "unconnected-(U5B-NC8-PadA8)") (class "Default")
      (node (ref "U5") (pin "A8") (pinfunction "NC8_A8") (pintype "passive+no_connect"))
    )
    (net (code "166") (name "unconnected-(U5B-NC9-PadA9)") (class "Default")
      (node (ref "U5") (pin "A9") (pinfunction "NC9_A9") (pintype "passive+no_connect"))
    )
    (net (code "167") (name "unconnected-(U5B-NC10-PadA10)") (class "Default")
      (node (ref "U5") (pin "A10") (pinfunction "NC10_A10") (pintype "passive+no_connect"))
    )
    (net (code "168") (name "unconnected-(U5B-NC11-PadA11)") (class "Default")
      (node (ref "U5") (pin "A11") (pinfunction "NC11_A11") (pintype "passive+no_connect"))
    )
    (net (code "169") (name "unconnected-(U5B-NC12-PadA12)") (class "Default")
      (node (ref "U5") (pin "A12") (pinfunction "NC12_A12") (pintype "passive+no_connect"))
    )
    (net (code "170") (name "unconnected-(U5B-NC13-PadA13)") (class "Default")
      (node (ref "U5") (pin "A13") (pinfunction "NC13_A13") (pintype "passive+no_connect"))
    )
    (net (code "171") (name "unconnected-(U5B-NC14-PadA14)") (class "Default")
      (node (ref "U5") (pin "A14") (pinfunction "NC14_A14") (pintype "passive+no_connect"))
    )
    (net (code "172") (name "unconnected-(U5B-NC15-PadB1)") (class "Default")
      (node (ref "U5") (pin "B1") (pinfunction "NC15_B1") (pintype "passive+no_connect"))
    )
    (net (code "173") (name "unconnected-(U5B-NC21-PadB7)") (class "Default")
      (node (ref "U5") (pin "B7") (pinfunction "NC21_B7") (pintype "passive+no_connect"))
    )
    (net (code "174") (name "unconnected-(U5B-NC22-PadB8)") (class "Default")
      (node (ref "U5") (pin "B8") (pinfunction "NC22_B8") (pintype "passive+no_connect"))
    )
    (net (code "175") (name "unconnected-(U5B-NC23-PadB9)") (class "Default")
      (node (ref "U5") (pin "B9") (pinfunction "NC23_B9") (pintype "passive+no_connect"))
    )
    (net (code "176") (name "unconnected-(U5B-NC24-PadB10)") (class "Default")
      (node (ref "U5") (pin "B10") (pinfunction "NC24_B10") (pintype "passive+no_connect"))
    )
    (net (code "177") (name "unconnected-(U5B-NC25-PadB11)") (class "Default")
      (node (ref "U5") (pin "B11") (pinfunction "NC25_B11") (pintype "passive+no_connect"))
    )
    (net (code "178") (name "unconnected-(U5B-NC26-PadB12)") (class "Default")
      (node (ref "U5") (pin "B12") (pinfunction "NC26_B12") (pintype "passive+no_connect"))
    )
    (net (code "179") (name "unconnected-(U5B-NC27-PadB13)") (class "Default")
      (node (ref "U5") (pin "B13") (pinfunction "NC27_B13") (pintype "passive+no_connect"))
    )
    (net (code "180") (name "unconnected-(U5B-NC28-PadB14)") (class "Default")
      (node (ref "U5") (pin "B14") (pinfunction "NC28_B14") (pintype "passive+no_connect"))
    )
    (net (code "181") (name "unconnected-(U5B-NC29-PadC1)") (class "Default")
      (node (ref "U5") (pin "C1") (pinfunction "NC29_C1") (pintype "passive+no_connect"))
    )
    (net (code "182") (name "unconnected-(U5B-NC31-PadC3)") (class "Default")
      (node (ref "U5") (pin "C3") (pinfunction "NC31_C3") (pintype "passive+no_connect"))
    )
    (net (code "183") (name "unconnected-(U5B-NC35-PadC7)") (class "Default")
      (node (ref "U5") (pin "C7") (pinfunction "NC35_C7") (pintype "passive+no_connect"))
    )
    (net (code "184") (name "unconnected-(U5B-NC36-PadC8)") (class "Default")
      (node (ref "U5") (pin "C8") (pinfunction "NC36_C8") (pintype "passive+no_connect"))
    )
    (net (code "185") (name "unconnected-(U5B-NC37-PadC9)") (class "Default")
      (node (ref "U5") (pin "C9") (pinfunction "NC37_C9") (pintype "passive+no_connect"))
    )
    (net (code "186") (name "unconnected-(U5B-NC38-PadC10)") (class "Default")
      (node (ref "U5") (pin "C10") (pinfunction "NC38_C10") (pintype "passive+no_connect"))
    )
    (net (code "187") (name "unconnected-(U5B-NC39-PadC11)") (class "Default")
      (node (ref "U5") (pin "C11") (pinfunction "NC39_C11") (pintype "passive+no_connect"))
    )
    (net (code "188") (name "unconnected-(U5B-NC40-PadC12)") (class "Default")
      (node (ref "U5") (pin "C12") (pinfunction "NC40_C12") (pintype "passive+no_connect"))
    )
    (net (code "189") (name "unconnected-(U5B-NC41-PadC13)") (class "Default")
      (node (ref "U5") (pin "C13") (pinfunction "NC41_C13") (pintype "passive+no_connect"))
    )
    (net (code "190") (name "unconnected-(U5B-NC42-PadC14)") (class "Default")
      (node (ref "U5") (pin "C14") (pinfunction "NC42_C14") (pintype "passive+no_connect"))
    )
    (net (code "191") (name "unconnected-(U5B-NC43-PadD1)") (class "Default")
      (node (ref "U5") (pin "D1") (pinfunction "NC43_D1") (pintype "passive+no_connect"))
    )
    (net (code "192") (name "unconnected-(U5B-NC44-PadD2)") (class "Default")
      (node (ref "U5") (pin "D2") (pinfunction "NC44_D2") (pintype "passive+no_connect"))
    )
    (net (code "193") (name "unconnected-(U5B-NC45-PadD3)") (class "Default")
      (node (ref "U5") (pin "D3") (pinfunction "NC45_D3") (pintype "passive+no_connect"))
    )
    (net (code "194") (name "unconnected-(U5B-NC46-PadD4)") (class "Default")
      (node (ref "U5") (pin "D4") (pinfunction "NC46_D4") (pintype "passive+no_connect"))
    )
    (net (code "195") (name "unconnected-(U5B-NC54-PadD12)") (class "Default")
      (node (ref "U5") (pin "D12") (pinfunction "NC54_D12") (pintype "passive+no_connect"))
    )
    (net (code "196") (name "unconnected-(U5B-NC55-PadD13)") (class "Default")
      (node (ref "U5") (pin "D13") (pinfunction "NC55_D13") (pintype "passive+no_connect"))
    )
    (net (code "197") (name "unconnected-(U5B-NC56-PadD14)") (class "Default")
      (node (ref "U5") (pin "D14") (pinfunction "NC56_D14") (pintype "passive+no_connect"))
    )
    (net (code "198") (name "unconnected-(U5B-NC57-PadE1)") (class "Default")
      (node (ref "U5") (pin "E1") (pinfunction "NC57_E1") (pintype "passive+no_connect"))
    )
    (net (code "199") (name "unconnected-(U5B-NC58-PadE2)") (class "Default")
      (node (ref "U5") (pin "E2") (pinfunction "NC58_E2") (pintype "passive+no_connect"))
    )
    (net (code "200") (name "unconnected-(U5B-NC59-PadE3)") (class "Default")
      (node (ref "U5") (pin "E3") (pinfunction "NC59_E3") (pintype "passive+no_connect"))
    )
    (net (code "201") (name "unconnected-(U5B-NC68-PadE12)") (class "Default")
      (node (ref "U5") (pin "E12") (pinfunction "NC68_E12") (pintype "passive+no_connect"))
    )
    (net (code "202") (name "unconnected-(U5B-NC69-PadE13)") (class "Default")
      (node (ref "U5") (pin "E13") (pinfunction "NC69_E13") (pintype "passive+no_connect"))
    )
    (net (code "203") (name "unconnected-(U5B-NC70-PadE14)") (class "Default")
      (node (ref "U5") (pin "E14") (pinfunction "NC70_E14") (pintype "passive+no_connect"))
    )
    (net (code "204") (name "unconnected-(U5B-NC71-PadF1)") (class "Default")
      (node (ref "U5") (pin "F1") (pinfunction "NC71_F1") (pintype "passive+no_connect"))
    )
    (net (code "205") (name "unconnected-(U5B-NC72-PadF2)") (class "Default")
      (node (ref "U5") (pin "F2") (pinfunction "NC72_F2") (pintype "passive+no_connect"))
    )
    (net (code "206") (name "unconnected-(U5B-NC73-PadF3)") (class "Default")
      (node (ref "U5") (pin "F3") (pinfunction "NC73_F3") (pintype "passive+no_connect"))
    )
    (net (code "207") (name "unconnected-(U5B-NC82-PadF12)") (class "Default")
      (node (ref "U5") (pin "F12") (pinfunction "NC82_F12") (pintype "passive+no_connect"))
    )
    (net (code "208") (name "unconnected-(U5B-NC83-PadF13)") (class "Default")
      (node (ref "U5") (pin "F13") (pinfunction "NC83_F13") (pintype "passive+no_connect"))
    )
    (net (code "209") (name "unconnected-(U5B-NC84-PadF14)") (class "Default")
      (node (ref "U5") (pin "F14") (pinfunction "NC84_F14") (pintype "passive+no_connect"))
    )
    (net (code "210") (name "unconnected-(U5B-NC85-PadG1)") (class "Default")
      (node (ref "U5") (pin "G1") (pinfunction "NC85_G1") (pintype "passive+no_connect"))
    )
    (net (code "211") (name "unconnected-(U5B-NC86-PadG2)") (class "Default")
      (node (ref "U5") (pin "G2") (pinfunction "NC86_G2") (pintype "passive+no_connect"))
    )
    (net (code "212") (name "unconnected-(U5B-NC96-PadG12)") (class "Default")
      (node (ref "U5") (pin "G12") (pinfunction "NC96_G12") (pintype "passive+no_connect"))
    )
    (net (code "213") (name "unconnected-(U5B-NC97-PadG13)") (class "Default")
      (node (ref "U5") (pin "G13") (pinfunction "NC97_G13") (pintype "passive+no_connect"))
    )
    (net (code "214") (name "unconnected-(U5B-NC98-PadG14)") (class "Default")
      (node (ref "U5") (pin "G14") (pinfunction "NC98_G14") (pintype "passive+no_connect"))
    )
    (net (code "215") (name "unconnected-(U5B-NC99-PadH1)") (class "Default")
      (node (ref "U5") (pin "H1") (pinfunction "NC99_H1") (pintype "passive+no_connect"))
    )
    (net (code "216") (name "unconnected-(U5B-NC100-PadH2)") (class "Default")
      (node (ref "U5") (pin "H2") (pinfunction "NC100_H2") (pintype "passive+no_connect"))
    )
    (net (code "217") (name "unconnected-(U5B-NC101-PadH3)") (class "Default")
      (node (ref "U5") (pin "H3") (pinfunction "NC101_H3") (pintype "passive+no_connect"))
    )
    (net (code "218") (name "unconnected-(U5B-NC110-PadH12)") (class "Default")
      (node (ref "U5") (pin "H12") (pinfunction "NC110_H12") (pintype "passive+no_connect"))
    )
    (net (code "219") (name "unconnected-(U5B-NC111-PadH13)") (class "Default")
      (node (ref "U5") (pin "H13") (pinfunction "NC111_H13") (pintype "passive+no_connect"))
    )
    (net (code "220") (name "unconnected-(U5B-NC112-PadH14)") (class "Default")
      (node (ref "U5") (pin "H14") (pinfunction "NC112_H14") (pintype "passive+no_connect"))
    )
    (net (code "221") (name "unconnected-(U5B-NC113-PadJ1)") (class "Default")
      (node (ref "U5") (pin "J1") (pinfunction "NC113_J1") (pintype "passive+no_connect"))
    )
    (net (code "222") (name "unconnected-(U5B-NC114-PadJ2)") (class "Default")
      (node (ref "U5") (pin "J2") (pinfunction "NC114_J2") (pintype "passive+no_connect"))
    )
    (net (code "223") (name "unconnected-(U5B-NC115-PadJ3)") (class "Default")
      (node (ref "U5") (pin "J3") (pinfunction "NC115_J3") (pintype "passive+no_connect"))
    )
    (net (code "224") (name "unconnected-(U5B-NC124-PadJ12)") (class "Default")
      (node (ref "U5") (pin "J12") (pinfunction "NC124_J12") (pintype "passive+no_connect"))
    )
    (net (code "225") (name "unconnected-(U5B-NC125-PadJ13)") (class "Default")
      (node (ref "U5") (pin "J13") (pinfunction "NC125_J13") (pintype "passive+no_connect"))
    )
    (net (code "226") (name "unconnected-(U5B-NC126-PadJ14)") (class "Default")
      (node (ref "U5") (pin "J14") (pinfunction "NC126_J14") (pintype "passive+no_connect"))
    )
    (net (code "227") (name "unconnected-(U5B-NC127-PadK1)") (class "Default")
      (node (ref "U5") (pin "K1") (pinfunction "NC127_K1") (pintype "passive+no_connect"))
    )
    (net (code "228") (name "unconnected-(U5B-NC128-PadK2)") (class "Default")
      (node (ref "U5") (pin "K2") (pinfunction "NC128_K2") (pintype "passive+no_connect"))
    )
    (net (code "229") (name "unconnected-(U5B-NC129-PadK3)") (class "Default")
      (node (ref "U5") (pin "K3") (pinfunction "NC129_K3") (pintype "passive+no_connect"))
    )
    (net (code "230") (name "unconnected-(U5B-NC138-PadK12)") (class "Default")
      (node (ref "U5") (pin "K12") (pinfunction "NC138_K12") (pintype "passive+no_connect"))
    )
    (net (code "231") (name "unconnected-(U5B-NC139-PadK13)") (class "Default")
      (node (ref "U5") (pin "K13") (pinfunction "NC139_K13") (pintype "passive+no_connect"))
    )
    (net (code "232") (name "unconnected-(U5B-NC140-PadK14)") (class "Default")
      (node (ref "U5") (pin "K14") (pinfunction "NC140_K14") (pintype "passive+no_connect"))
    )
    (net (code "233") (name "unconnected-(U5B-NC141-PadL1)") (class "Default")
      (node (ref "U5") (pin "L1") (pinfunction "NC141_L1") (pintype "passive+no_connect"))
    )
    (net (code "234") (name "unconnected-(U5B-NC142-PadL2)") (class "Default")
      (node (ref "U5") (pin "L2") (pinfunction "NC142_L2") (pintype "passive+no_connect"))
    )
    (net (code "235") (name "unconnected-(U5B-NC143-PadL3)") (class "Default")
      (node (ref "U5") (pin "L3") (pinfunction "NC143_L3") (pintype "passive+no_connect"))
    )
    (net (code "236") (name "unconnected-(U5B-NC152-PadL12)") (class "Default")
      (node (ref "U5") (pin "L12") (pinfunction "NC152_L12") (pintype "passive+no_connect"))
    )
    (net (code "237") (name "unconnected-(U5B-NC153-PadL13)") (class "Default")
      (node (ref "U5") (pin "L13") (pinfunction "NC153_L13") (pintype "passive+no_connect"))
    )
    (net (code "238") (name "unconnected-(U5B-NC154-PadL14)") (class "Default")
      (node (ref "U5") (pin "L14") (pinfunction "NC154_L14") (pintype "passive+no_connect"))
    )
    (net (code "239") (name "unconnected-(U5B-NC155-PadM1)") (class "Default")
      (node (ref "U5") (pin "M1") (pinfunction "NC155_M1") (pintype "passive+no_connect"))
    )
    (net (code "240") (name "unconnected-(U5B-NC156-PadM2)") (class "Default")
      (node (ref "U5") (pin "M2") (pinfunction "NC156_M2") (pintype "passive+no_connect"))
    )
    (net (code "241") (name "unconnected-(U5B-NC157-PadM3)") (class "Default")
      (node (ref "U5") (pin "M3") (pinfunction "NC157_M3") (pintype "passive+no_connect"))
    )
    (net (code "242") (name "unconnected-(U5B-NC161-PadM7)") (class "Default")
      (node (ref "U5") (pin "M7") (pinfunction "NC161_M7") (pintype "passive+no_connect"))
    )
    (net (code "243") (name "unconnected-(U5B-NC162-PadM8)") (class "Default")
      (node (ref "U5") (pin "M8") (pinfunction "NC162_M8") (pintype "passive+no_connect"))
    )
    (net (code "244") (name "unconnected-(U5B-NC163-PadM9)") (class "Default")
      (node (ref "U5") (pin "M9") (pinfunction "NC163_M9") (pintype "passive+no_connect"))
    )
    (net (code "245") (name "unconnected-(U5B-NC164-PadM10)") (class "Default")
      (node (ref "U5") (pin "M10") (pinfunction "NC164_M10") (pintype "passive+no_connect"))
    )
    (net (code "246") (name "unconnected-(U5B-NC165-PadM11)") (class "Default")
      (node (ref "U5") (pin "M11") (pinfunction "NC165_M11") (pintype "passive+no_connect"))
    )
    (net (code "247") (name "unconnected-(U5B-NC166-PadM12)") (class "Default")
      (node (ref "U5") (pin "M12") (pinfunction "NC166_M12") (pintype "passive+no_connect"))
    )
    (net (code "248") (name "unconnected-(U5B-NC167-PadM13)") (class "Default")
      (node (ref "U5") (pin "M13") (pinfunction "NC167_M13") (pintype "passive+no_connect"))
    )
    (net (code "249") (name "unconnected-(U5B-NC168-PadM14)") (class "Default")
      (node (ref "U5") (pin "M14") (pinfunction "NC168_M14") (pintype "passive+no_connect"))
    )
    (net (code "250") (name "unconnected-(U5B-NC169-PadN1)") (class "Default")
      (node (ref "U5") (pin "N1") (pinfunction "NC169_N1") (pintype "passive+no_connect"))
    )
    (net (code "251") (name "unconnected-(U5B-NC171-PadN3)") (class "Default")
      (node (ref "U5") (pin "N3") (pinfunction "NC171_N3") (pintype "passive+no_connect"))
    )
    (net (code "252") (name "unconnected-(U5B-NC174-PadN6)") (class "Default")
      (node (ref "U5") (pin "N6") (pinfunction "NC174_N6") (pintype "passive+no_connect"))
    )
    (net (code "253") (name "unconnected-(U5B-NC175-PadN7)") (class "Default")
      (node (ref "U5") (pin "N7") (pinfunction "NC175_N7") (pintype "passive+no_connect"))
    )
    (net (code "254") (name "unconnected-(U5B-NC176-PadN8)") (class "Default")
      (node (ref "U5") (pin "N8") (pinfunction "NC176_N8") (pintype "passive+no_connect"))
    )
    (net (code "255") (name "unconnected-(U5B-NC177-PadN9)") (class "Default")
      (node (ref "U5") (pin "N9") (pinfunction "NC177_N9") (pintype "passive+no_connect"))
    )
    (net (code "256") (name "unconnected-(U5B-NC178-PadN10)") (class "Default")
      (node (ref "U5") (pin "N10") (pinfunction "NC178_N10") (pintype "passive+no_connect"))
    )
    (net (code "257") (name "unconnected-(U5B-NC179-PadN11)") (class "Default")
      (node (ref "U5") (pin "N11") (pinfunction "NC179_N11") (pintype "passive+no_connect"))
    )
    (net (code "258") (name "unconnected-(U5B-NC180-PadN12)") (class "Default")
      (node (ref "U5") (pin "N12") (pinfunction "NC180_N12") (pintype "passive+no_connect"))
    )
    (net (code "259") (name "unconnected-(U5B-NC181-PadN13)") (class "Default")
      (node (ref "U5") (pin "N13") (pinfunction "NC181_N13") (pintype "passive+no_connect"))
    )
    (net (code "260") (name "unconnected-(U5B-NC182-PadN14)") (class "Default")
      (node (ref "U5") (pin "N14") (pinfunction "NC182_N14") (pintype "passive+no_connect"))
    )
    (net (code "261") (name "unconnected-(U5B-NC183-PadP1)") (class "Default")
      (node (ref "U5") (pin "P1") (pinfunction "NC183_P1") (pintype "passive+no_connect"))
    )
    (net (code "262") (name "unconnected-(U5B-NC184-PadP2)") (class "Default")
      (node (ref "U5") (pin "P2") (pinfunction "NC184_P2") (pintype "passive+no_connect"))
    )
    (net (code "263") (name "unconnected-(U5B-NC190-PadP8)") (class "Default")
      (node (ref "U5") (pin "P8") (pinfunction "NC190_P8") (pintype "passive+no_connect"))
    )
    (net (code "264") (name "unconnected-(U5B-NC191-PadP9)") (class "Default")
      (node (ref "U5") (pin "P9") (pinfunction "NC191_P9") (pintype "passive+no_connect"))
    )
    (net (code "265") (name "unconnected-(U5B-NC193-PadP11)") (class "Default")
      (node (ref "U5") (pin "P11") (pinfunction "NC193_P11") (pintype "passive+no_connect"))
    )
    (net (code "266") (name "unconnected-(U5B-NC194-PadP12)") (class "Default")
      (node (ref "U5") (pin "P12") (pinfunction "NC194_P12") (pintype "passive+no_connect"))
    )
    (net (code "267") (name "unconnected-(U5B-NC195-PadP13)") (class "Default")
      (node (ref "U5") (pin "P13") (pinfunction "NC195_P13") (pintype "passive+no_connect"))
    )
    (net (code "268") (name "unconnected-(U5B-NC196-PadP14)") (class "Default")
      (node (ref "U5") (pin "P14") (pinfunction "NC196_P14") (pintype "passive+no_connect"))
    )
    (net (code "269") (name "unconnected-(U5B-RFU1-PadA7)") (class "Default")
      (node (ref "U5") (pin "A7") (pinfunction "RFU1_A7") (pintype "passive+no_connect"))
    )
    (net (code "270") (name "unconnected-(U5B-RFU2-PadE5)") (class "Default")
      (node (ref "U5") (pin "E5") (pinfunction "RFU2_E5") (pintype "passive+no_connect"))
    )
    (net (code "271") (name "unconnected-(U5B-RFU3-PadE8)") (class "Default")
      (node (ref "U5") (pin "E8") (pinfunction "RFU3_E8") (pintype "passive+no_connect"))
    )
    (net (code "272") (name "unconnected-(U5B-RFU4-PadG3)") (class "Default")
      (node (ref "U5") (pin "G3") (pinfunction "RFU4_G3") (pintype "passive+no_connect"))
    )
    (net (code "273") (name "unconnected-(U5B-RFU5-PadG10)") (class "Default")
      (node (ref "U5") (pin "G10") (pinfunction "RFU5_G10") (pintype "passive+no_connect"))
    )
    (net (code "274") (name "unconnected-(U5B-RFU6-PadK6)") (class "Default")
      (node (ref "U5") (pin "K6") (pinfunction "RFU6_K6") (pintype "passive+no_connect"))
    )
    (net (code "275") (name "unconnected-(U5B-RFU7-PadK7)") (class "Default")
      (node (ref "U5") (pin "K7") (pinfunction "RFU7_K7") (pintype "passive+no_connect"))
    )
    (net (code "276") (name "unconnected-(U5B-RFU8-PadP7)") (class "Default")
      (node (ref "U5") (pin "P7") (pinfunction "RFU8_P7") (pintype "passive+no_connect"))
    )
    (net (code "277") (name "unconnected-(U5B-RFU9-PadP10)") (class "Default")
      (node (ref "U5") (pin "P10") (pinfunction "RFU9_P10") (pintype "passive+no_connect"))
    )
    (net (code "278") (name "unconnected-(U6-NC-Pad5)") (class "Default")
      (node (ref "U6") (pin "5") (pinfunction "NC_5") (pintype "passive+no_connect"))
    )
    (net (code "279") (name "unconnected-(U6-NC-Pad6)") (class "Default")
      (node (ref "U6") (pin "6") (pinfunction "NC_6") (pintype "passive+no_connect"))
    )
  )
)
